# filament-width-sensor.net
KiCad netlist of a schematic drawn in Altium Designer
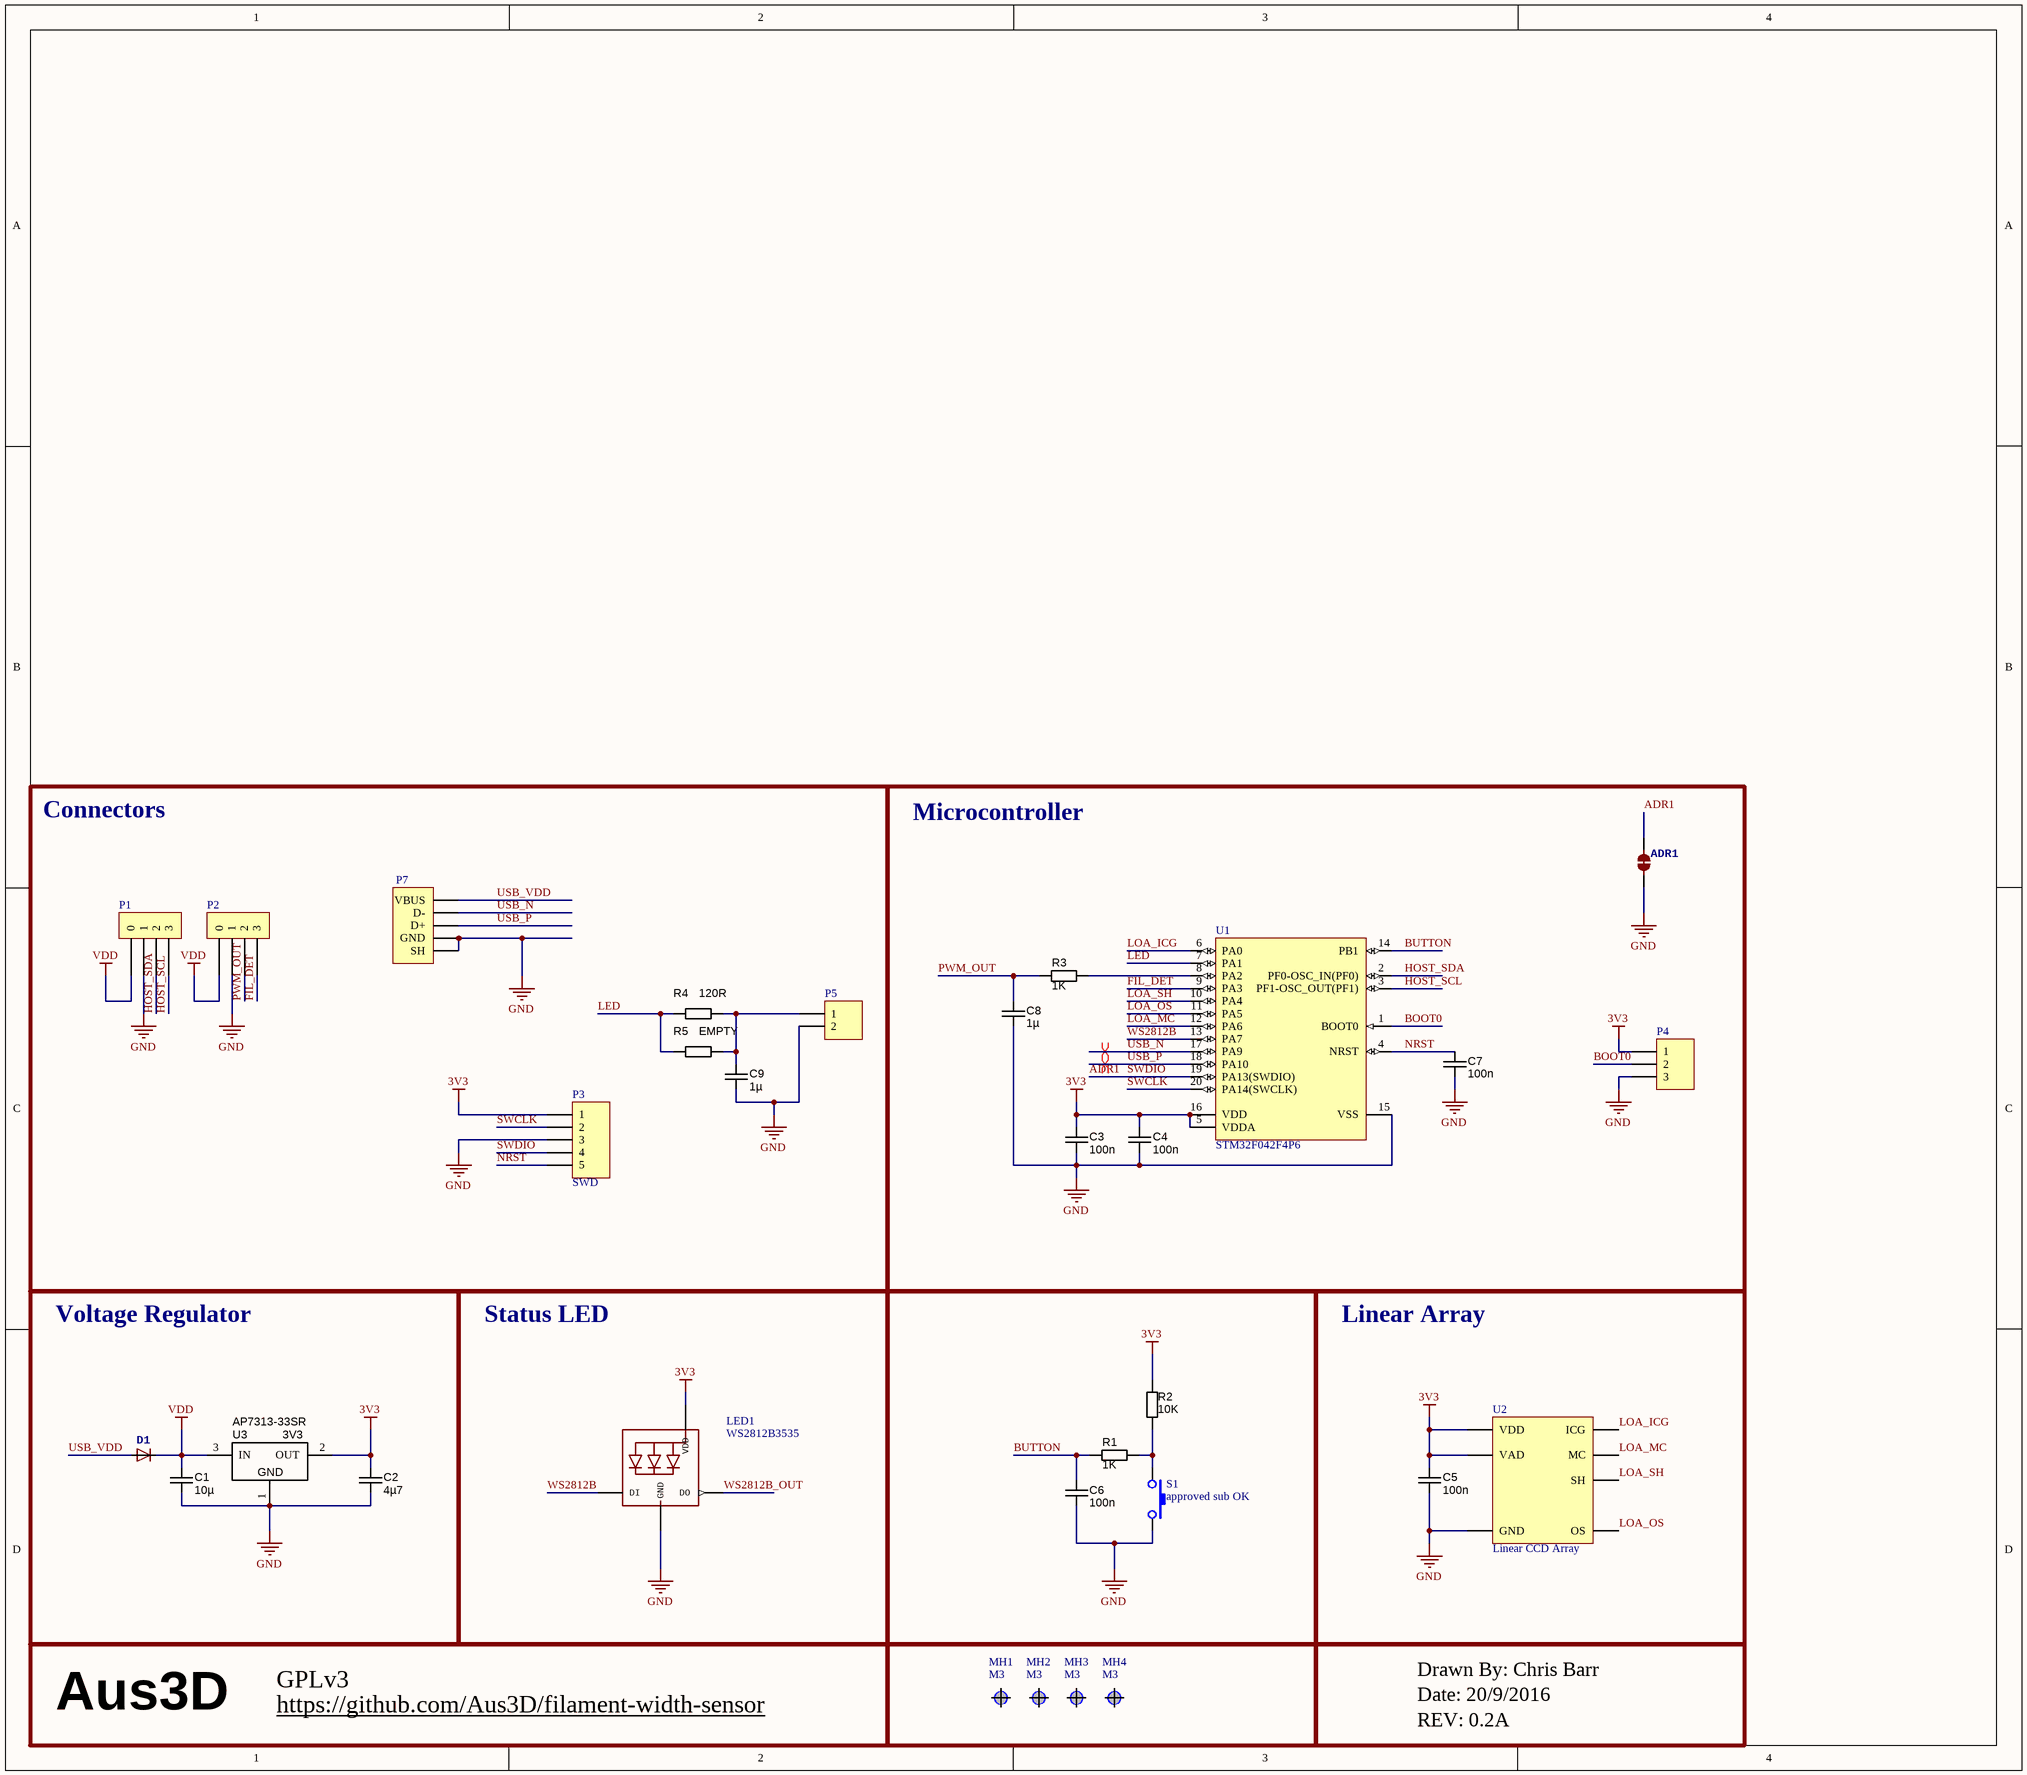
[diagram p0: filament-width-sensor.SchDoc]

(export (version "E")
  (design (tool "Eeschema 10.0.6"))
  (components
    (comp (ref "ADR1")
      (value "JUMPER-PAD-2-NC_BY_TRACE")
      (footprint "PAD-JUMPER-2-NC_BY_TRACE_YES_SILK")
      (libsource (lib "SparkFun-Passives") (part "JUMPER-PAD-2-NC_BY_TRACE"))
    )
    (comp (ref "C1")
      (value "10µ")
      (footprint "CAPC2012X135N")
      (description "Capacitor SMD Cer 10uF 10% 10V X5R 0805")
      (fields (field (name "TOLERANCE") "±10%") (field (name "Comment") "approved sub OK"))
      (libsource (lib "PBL - Capacitors") (part "CAPC_10u_0805_10V"))
    )
    (comp (ref "C2")
      (value "4µ7")
      (footprint "CAPC2012X135N")
      (description "Capacitor SMD Cer 4.7uF 10% 16V X5R 0805")
      (fields (field (name "TOLERANCE") "±10%") (field (name "Comment") "approved sub OK"))
      (libsource (lib "PBL - Capacitors") (part "CAPC_4u7_0805"))
    )
    (comp (ref "C3")
      (value "100n")
      (footprint "CAPC1608X90N")
      (description "Capacitor SMD Cer 100nF 10% 50V X7R 0603")
      (fields (field (name "TOLERANCE") "±10%") (field (name "Comment") "approved sub OK"))
      (libsource (lib "PBL - Capacitors") (part "CAPC_100n_0603_X7R_50V_10%"))
    )
    (comp (ref "C4")
      (value "100n")
      (footprint "CAPC1608X90N")
      (description "Capacitor SMD Cer 100nF 10% 50V X7R 0603")
      (fields (field (name "TOLERANCE") "±10%") (field (name "Comment") "approved sub OK"))
      (libsource (lib "PBL - Capacitors") (part "CAPC_100n_0603_X7R_50V_10%"))
    )
    (comp (ref "C5")
      (value "100n")
      (footprint "CAPC1608X90N")
      (description "Capacitor SMD Cer 100nF 10% 50V X7R 0603")
      (fields (field (name "TOLERANCE") "±10%") (field (name "Comment") "approved sub OK"))
      (libsource (lib "PBL - Capacitors") (part "CAPC_100n_0603_X7R_50V_10%"))
    )
    (comp (ref "C6")
      (value "100n")
      (footprint "CAPC1608X90N")
      (description "Capacitor SMD Cer 100nF 10% 50V X7R 0603")
      (fields (field (name "TOLERANCE") "±10%") (field (name "Comment") "approved sub OK"))
      (libsource (lib "PBL - Capacitors") (part "CAPC_100n_0603_X7R_50V_10%"))
    )
    (comp (ref "C7")
      (value "100n")
      (footprint "CAPC1608X90N")
      (description "Capacitor SMD Cer 100nF 10% 50V X7R 0603")
      (fields (field (name "TOLERANCE") "±10%") (field (name "Comment") "approved sub OK"))
      (libsource (lib "PBL - Capacitors") (part "CAPC_100n_0603_X7R_50V_10%"))
    )
    (comp (ref "C8")
      (value "1µ")
      (footprint "CAPC1608X90N")
      (description "Capacitor SMD Cer 1uF 10% 16V X7R 0603")
      (fields (field (name "TOLERANCE") "±10%") (field (name "Comment") "approved sub OK"))
      (libsource (lib "PBL - Capacitors") (part "CAPC_1u_0603_X7R_16V_10%"))
    )
    (comp (ref "C9")
      (value "1µ")
      (footprint "CAPC1608X90N")
      (description "Capacitor SMD Cer 1uF 10% 16V X7R 0603")
      (fields (field (name "TOLERANCE") "±10%") (field (name "Comment") "approved sub OK"))
      (libsource (lib "PBL - Capacitors") (part "CAPC_1u_0603_X7R_16V_10%"))
    )
    (comp (ref "D1")
      (value "approved sub OK")
      (footprint "SOT23-R")
      (description "Diode SMA")
      (libsource (lib "adafruit") (part "DIODESOT23_REFLOW"))
    )
    (comp (ref "LED1")
      (value "WS2812B3535")
      (footprint "LED3535")
      (description "Smart RGB LED")
      (libsource (lib "adafruit") (part "WS2812B3535"))
    )
    (comp (ref "MH1") (value "M3") (footprint "M3-Hole-2") (libsource (lib "Schlib1") (part "Screw Hole")))
    (comp (ref "MH2") (value "M3") (footprint "M3-Hole-2") (libsource (lib "Schlib1") (part "Screw Hole")))
    (comp (ref "MH3") (value "M3") (footprint "M3-Hole-2") (libsource (lib "Schlib1") (part "Screw Hole")))
    (comp (ref "MH4") (value "M3") (footprint "M3-Hole-2") (libsource (lib "Schlib1") (part "Screw Hole")))
    (comp (ref "P1")
      (value "approved sub OK")
      (footprint "SM04B-SRSS-TB")
      (description "JST-SH 4-pin")
      (libsource (lib "Schlib1") (part "SM04B-SRSS-TB"))
    )
    (comp (ref "P2")
      (value "approved sub OK")
      (footprint "SM04B-SRSS-TB")
      (description "JST-SH 4-pin")
      (libsource (lib "Schlib1") (part "SM04B-SRSS-TB"))
    )
    (comp (ref "P3")
      (value "SWD")
      (footprint "HDR1X5")
      (description "Header, 5-Pin")
      (fields (field (name "PUBLISHER") "Altium Limited"))
      (libsource (lib "Miscellaneous Connectors") (part "Header 5"))
    )
    (comp (ref "P4")
      (value "approved sub OK")
      (footprint "HDR1X3")
      (description "Header, 3-Pin")
      (fields (field (name "PUBLISHER") "Altium Limited"))
      (libsource (lib "Miscellaneous Connectors") (part "Header 3"))
    )
    (comp (ref "P5")
      (value "approved sub OK")
      (footprint "HDR1X2")
      (description "Header, 2-Pin")
      (fields (field (name "PUBLISHER") "Altium Limited"))
      (libsource (lib "Miscellaneous Connectors") (part "Header 2"))
    )
    (comp (ref "P7")
      (value "approved sub OK")
      (footprint "Micro-USB B Molex 105017-0001")
      (description "Micro-USB B Socket")
      (libsource (lib "Schlib1") (part "Micro-USB B Socket"))
    )
    (comp (ref "R1")
      (value "1K")
      (footprint "RESC1608X55N")
      (description "Resistor SMD chip 1k Ohm 0.1W 5% 0603")
      (fields (field (name "TOLERANCE") "±5%") (field (name "Comment") "Thick Film"))
      (libsource (lib "PBL - Resistors") (part "RES_1K_0603_5%"))
    )
    (comp (ref "R2")
      (value "10K")
      (footprint "RESC1608X55N")
      (description "Resistor SMD chip 10k Ohm 0.1W 5% 0603")
      (fields (field (name "TOLERANCE") "±5%") (field (name "Comment") "Thick Film"))
      (libsource (lib "PBL - Resistors") (part "RES_10K_0603_5%"))
    )
    (comp (ref "R3")
      (value "1K")
      (footprint "RESC1608X55N")
      (description "Resistor SMD chip 1k Ohm 0.1W 5% 0603")
      (fields (field (name "TOLERANCE") "±5%") (field (name "Comment") "Thick Film"))
      (libsource (lib "PBL - Resistors") (part "RES_1K_0603_5%"))
    )
    (comp (ref "R4")
      (value "120R")
      (footprint "RESC1608X55N")
      (description "Resistor SMD chip 120 Ohm 0.1W 5% 0603")
      (fields (field (name "TOLERANCE") "±5%") (field (name "Comment") "Thick Film"))
      (libsource (lib "PBL - Resistors") (part "RES_120R_0603_5%"))
    )
    (comp (ref "R5")
      (value "EMPTY")
      (footprint "RESC1608X55N")
      (description "Resistor, 08603 SMD, Empty footprint")
      (fields (field (name "Comment") "RES_EMPTY_0603"))
      (libsource (lib "PBL - Resistors") (part "RES_EMPTY_0603"))
    )
    (comp (ref "S1")
      (value "approved sub OK")
      (footprint "SW-PB SMD 2pin")
      (description "SMD Button")
      (libsource (lib "RUMBA_v2") (part "SW-PB"))
    )
    (comp (ref "U1")
      (value "STM32F042F4P6")
      (footprint "STM-TSSOP20_N")
      (libsource (lib "STMicroelectronics STM32 F0") (part "STM32F030F4P6"))
    )
    (comp (ref "U2")
      (value "Linear CCD Array")
      (footprint "TCD1304AP Linear CCD")
      (description "Toshiba CCD Array TCD1304AP")
      (libsource (lib "Schlib1") (part "TCD1304AP"))
    )
    (comp (ref "U3")
      (value "AP7313-33SR")
      (footprint "SOT23-3")
      (description "Voltage Regulator 3.3V LDO SOT23R-3 SMD")
      (fields (field (name "TOLERANCE") "±2%") (field (name "ALTIUM_VALUE") "3V3"))
      (libsource (lib "PBL - Regulators") (part "VREG_3V3_AP7313-33SR"))
    )
  )
  (nets
    (net (code "1") (name "/ADR1") (class "Default")
      (node (ref "ADR1") (pin "2") (pinfunction "2_2") (pintype "passive"))
      (node (ref "P3") (pin "4") (pinfunction "4_4") (pintype "passive"))
      (node (ref "U1") (pin "19") (pinfunction "PA13(SWDIO)_19") (pintype "bidirectional"))
    )
    (net (code "2") (name "/BOOT0") (class "Default")
      (node (ref "P4") (pin "2") (pinfunction "2_2") (pintype "passive"))
      (node (ref "U1") (pin "1") (pinfunction "BOOT0_1") (pintype "input"))
    )
    (net (code "3") (name "/BUTTON") (class "Default")
      (node (ref "C6") (pin "1") (pintype "passive"))
      (node (ref "R1") (pin "1") (pinfunction "1_1") (pintype "passive"))
      (node (ref "U1") (pin "14") (pinfunction "PB1_14") (pintype "bidirectional"))
    )
    (net (code "4") (name "/FIL_DET") (class "Default")
      (node (ref "P2") (pin "3") (pinfunction "3_3") (pintype "passive"))
      (node (ref "U1") (pin "9") (pinfunction "PA3_9") (pintype "bidirectional"))
    )
    (net (code "5") (name "/HOST_SCL") (class "Default")
      (node (ref "P1") (pin "3") (pinfunction "3_3") (pintype "passive"))
      (node (ref "U1") (pin "3") (pinfunction "PF1-OSC_OUT(PF1)_3") (pintype "bidirectional"))
    )
    (net (code "6") (name "/HOST_SDA") (class "Default")
      (node (ref "P1") (pin "2") (pinfunction "2_2") (pintype "passive"))
      (node (ref "U1") (pin "2") (pinfunction "PF0-OSC_IN(PF0)_2") (pintype "bidirectional"))
    )
    (net (code "7") (name "/LED") (class "Default")
      (node (ref "R4") (pin "1") (pinfunction "1_1") (pintype "passive"))
      (node (ref "R5") (pin "1") (pinfunction "1_1") (pintype "passive"))
      (node (ref "U1") (pin "7") (pinfunction "PA1_7") (pintype "bidirectional"))
    )
    (net (code "8") (name "/LOA_ICG") (class "Default")
      (node (ref "U1") (pin "6") (pinfunction "PA0_6") (pintype "bidirectional"))
      (node (ref "U2") (pin "ICG") (pinfunction "ICG_ICG") (pintype "passive"))
    )
    (net (code "9") (name "/LOA_MC") (class "Default")
      (node (ref "U1") (pin "12") (pinfunction "PA6_12") (pintype "bidirectional"))
      (node (ref "U2") (pin "MC") (pinfunction "MC_MC") (pintype "passive"))
    )
    (net (code "10") (name "/LOA_OS") (class "Default")
      (node (ref "U1") (pin "11") (pinfunction "PA5_11") (pintype "bidirectional"))
      (node (ref "U2") (pin "OS") (pinfunction "OS_OS") (pintype "passive"))
    )
    (net (code "11") (name "/LOA_SH") (class "Default")
      (node (ref "U1") (pin "10") (pinfunction "PA4_10") (pintype "bidirectional"))
      (node (ref "U2") (pin "SH") (pinfunction "SH_SH") (pintype "passive"))
    )
    (net (code "12") (name "/NRST") (class "Default")
      (node (ref "C7") (pin "1") (pintype "passive"))
      (node (ref "P3") (pin "5") (pinfunction "5_5") (pintype "passive"))
      (node (ref "U1") (pin "4") (pinfunction "NRST_4") (pintype "bidirectional"))
    )
    (net (code "13") (name "/PWM_OUT") (class "Default")
      (node (ref "C8") (pin "1") (pintype "passive"))
      (node (ref "P2") (pin "2") (pinfunction "2_2") (pintype "passive"))
      (node (ref "R3") (pin "1") (pinfunction "1_1") (pintype "passive"))
    )
    (net (code "14") (name "/SWCLK") (class "Default")
      (node (ref "P3") (pin "2") (pinfunction "2_2") (pintype "passive"))
      (node (ref "U1") (pin "20") (pinfunction "PA14(SWCLK)_20") (pintype "bidirectional"))
    )
    (net (code "15") (name "/USB_N") (class "Default")
      (node (ref "P7") (pin "D-") (pinfunction "D-_D-") (pintype "passive"))
      (node (ref "U1") (pin "17") (pinfunction "PA9_17") (pintype "bidirectional"))
    )
    (net (code "16") (name "/USB_P") (class "Default")
      (node (ref "P7") (pin "D+") (pinfunction "D+_D+") (pintype "passive"))
      (node (ref "U1") (pin "18") (pinfunction "PA10_18") (pintype "bidirectional"))
    )
    (net (code "17") (name "/USB_VDD") (class "Default")
      (node (ref "D1") (pin "1") (pinfunction "A_1") (pintype "passive"))
      (node (ref "P7") (pin "VBUS") (pinfunction "VBUS_VBUS") (pintype "passive"))
    )
    (net (code "18") (name "/WS2812B") (class "Default")
      (node (ref "LED1") (pin "1") (pinfunction "DI_1") (pintype "passive"))
      (node (ref "U1") (pin "13") (pinfunction "PA7_13") (pintype "bidirectional"))
    )
    (net (code "19") (name "/WS2812B_OUT") (class "Default")
      (node (ref "LED1") (pin "3") (pinfunction "DO_3") (pintype "output"))
    )
    (net (code "20") (name "3V3") (class "Default")
      (node (ref "C2") (pin "1") (pintype "passive"))
      (node (ref "C3") (pin "1") (pintype "passive"))
      (node (ref "C4") (pin "1") (pintype "passive"))
      (node (ref "C5") (pin "1") (pintype "passive"))
      (node (ref "LED1") (pin "2") (pinfunction "VDD_2") (pintype "power_in"))
      (node (ref "P3") (pin "1") (pinfunction "1_1") (pintype "passive"))
      (node (ref "P4") (pin "1") (pinfunction "1_1") (pintype "passive"))
      (node (ref "R2") (pin "1") (pinfunction "1_1") (pintype "passive"))
      (node (ref "U1") (pin "16") (pinfunction "VDD_16") (pintype "power_in"))
      (node (ref "U1") (pin "5") (pinfunction "VDDA_5") (pintype "power_in"))
      (node (ref "U2") (pin "VAD") (pinfunction "VAD_VAD") (pintype "passive"))
      (node (ref "U2") (pin "VDD") (pinfunction "VDD_VDD") (pintype "passive"))
      (node (ref "U3") (pin "2") (pinfunction "OUT_2") (pintype "power_in"))
    )
    (net (code "21") (name "GND") (class "Default")
      (node (ref "ADR1") (pin "1") (pinfunction "1_1") (pintype "passive"))
      (node (ref "C1") (pin "2") (pintype "passive"))
      (node (ref "C2") (pin "2") (pintype "passive"))
      (node (ref "C3") (pin "2") (pintype "passive"))
      (node (ref "C4") (pin "2") (pintype "passive"))
      (node (ref "C5") (pin "2") (pintype "passive"))
      (node (ref "C6") (pin "2") (pintype "passive"))
      (node (ref "C7") (pin "2") (pintype "passive"))
      (node (ref "C8") (pin "2") (pintype "passive"))
      (node (ref "C9") (pin "2") (pintype "passive"))
      (node (ref "LED1") (pin "4") (pinfunction "GND_4") (pintype "power_in"))
      (node (ref "P1") (pin "1") (pinfunction "1_1") (pintype "passive"))
      (node (ref "P2") (pin "1") (pinfunction "1_1") (pintype "passive"))
      (node (ref "P3") (pin "3") (pinfunction "3_3") (pintype "passive"))
      (node (ref "P4") (pin "3") (pinfunction "3_3") (pintype "passive"))
      (node (ref "P5") (pin "2") (pinfunction "2_2") (pintype "passive"))
      (node (ref "P7") (pin "GND") (pinfunction "GND_GND") (pintype "passive"))
      (node (ref "P7") (pin "SHIELD") (pinfunction "SH_SHIELD") (pintype "passive"))
      (node (ref "S1") (pin "2") (pintype "passive"))
      (node (ref "U1") (pin "15") (pinfunction "VSS_15") (pintype "power_in"))
      (node (ref "U2") (pin "GND") (pinfunction "GND_GND") (pintype "passive"))
      (node (ref "U3") (pin "1") (pinfunction "GND_1") (pintype "power_in"))
    )
    (net (code "22") (name "Net-(C9-Pad1)") (class "Default")
      (node (ref "C9") (pin "1") (pintype "passive"))
      (node (ref "P5") (pin "1") (pinfunction "1_1") (pintype "passive"))
      (node (ref "R4") (pin "2") (pinfunction "2_2") (pintype "passive"))
      (node (ref "R5") (pin "2") (pinfunction "2_2") (pintype "passive"))
    )
    (net (code "23") (name "Net-(R1-Pad2)") (class "Default")
      (node (ref "R1") (pin "2") (pinfunction "2_2") (pintype "passive"))
      (node (ref "R2") (pin "2") (pinfunction "2_2") (pintype "passive"))
      (node (ref "S1") (pin "1") (pintype "passive"))
    )
    (net (code "24") (name "Net-(U1-PA2)") (class "Default")
      (node (ref "R3") (pin "2") (pinfunction "2_2") (pintype "passive"))
      (node (ref "U1") (pin "8") (pinfunction "PA2_8") (pintype "bidirectional"))
    )
    (net (code "25") (name "VDD") (class "Default")
      (node (ref "C1") (pin "1") (pintype "passive"))
      (node (ref "D1") (pin "3") (pinfunction "C_3") (pintype "passive"))
      (node (ref "P1") (pin "0") (pinfunction "0_0") (pintype "passive"))
      (node (ref "P2") (pin "0") (pinfunction "0_0") (pintype "passive"))
      (node (ref "U3") (pin "3") (pinfunction "IN_3") (pintype "power_in"))
    )
    (net (code "26") (name "unconnected-(MH1-0-PadM3)") (class "Default")
      (node (ref "MH1") (pin "M3") (pinfunction "0_M3") (pintype "passive"))
    )
    (net (code "27") (name "unconnected-(MH2-0-PadM3)") (class "Default")
      (node (ref "MH2") (pin "M3") (pinfunction "0_M3") (pintype "passive"))
    )
    (net (code "28") (name "unconnected-(MH3-0-PadM3)") (class "Default")
      (node (ref "MH3") (pin "M3") (pinfunction "0_M3") (pintype "passive"))
    )
    (net (code "29") (name "unconnected-(MH4-0-PadM3)") (class "Default")
      (node (ref "MH4") (pin "M3") (pinfunction "0_M3") (pintype "passive"))
    )
  )
)
